# pH_mini_v30.net
KiCad netlist of a schematic drawn in EAGLE
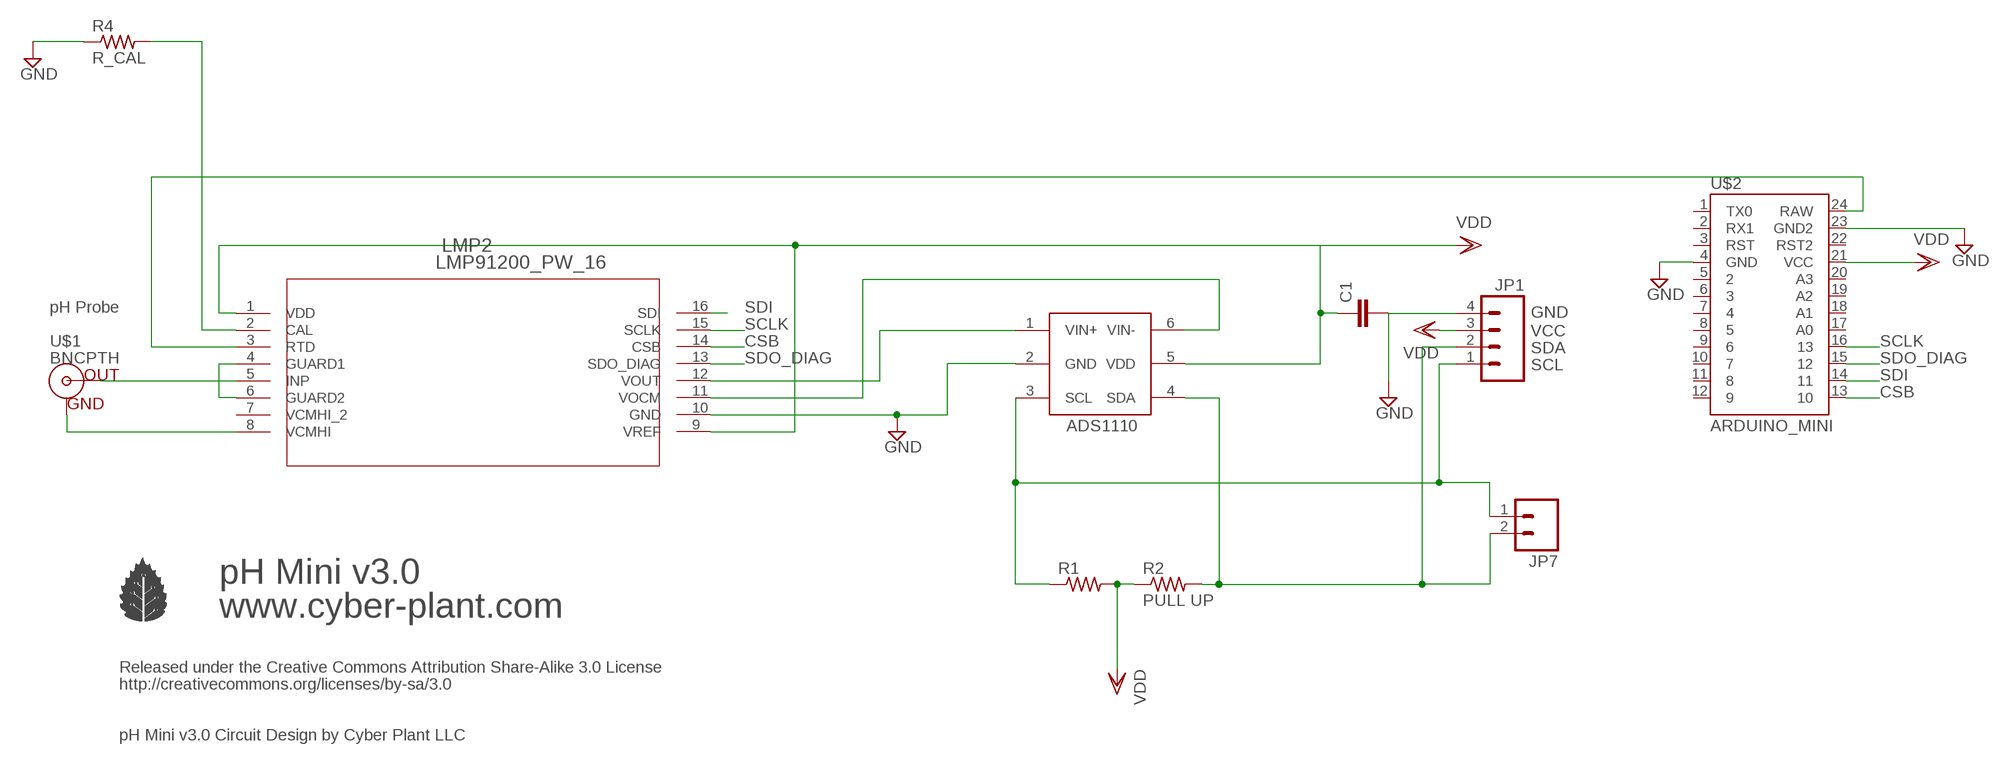
[diagram p0: schematic, sheet 1]

(export (version "E")
  (design (tool "Eeschema 10.0.6"))
  (components
    (comp (ref "C1")
      (value "CAP1206")
      (footprint "eagle-import:1206")
      (libsource (lib "eagle-import") (part "CAP1206"))
    )
    (comp (ref "IC1")
      (value "ADS1110")
      (footprint "eagle-import:SOT-23-6")
      (libsource (lib "eagle-import") (part "ADS1110"))
    )
    (comp (ref "JP1")
      (value "M04PTH")
      (footprint "eagle-import:1X04")
      (libsource (lib "eagle-import") (part "M04PTH"))
    )
    (comp (ref "JP7")
      (value "M02PTH")
      (footprint "eagle-import:1X02")
      (libsource (lib "eagle-import") (part "M02PTH"))
    )
    (comp (ref "LMP2")
      (value "LMP91200_PW_16")
      (footprint "eagle-import:MTC16")
      (fields
        (field (name "MANUFACTURER") "Texas Instruments")
        (field (name "MANUFACTURER_PART_NUMBER") "lmp91200_pw_16")
      )
      (libsource (lib "eagle-import") (part "LMP91200_PW_16"))
    )
    (comp (ref "R1")
      (value "R-US_0207/10")
      (footprint "eagle-import:0207_10")
      (libsource (lib "eagle-import") (part "R-US_0207/10"))
    )
    (comp (ref "R2")
      (value "PULL UP")
      (footprint "eagle-import:0207_10")
      (libsource (lib "eagle-import") (part "R-US_0207/10"))
    )
    (comp (ref "R4")
      (value "R_CAL")
      (footprint "eagle-import:0207_10")
      (libsource (lib "eagle-import") (part "R-US_0207/10"))
    )
    (comp (ref "U$1")
      (value "BNCPTH")
      (footprint "eagle-import:BNC")
      (libsource (lib "eagle-import") (part "BNCPTH"))
    )
    (comp (ref "U$2")
      (value "ARDUINO_MINI")
      (footprint "eagle-import:ARDUINO_MINI")
      (libsource (lib "eagle-import") (part "ARDUINO_MINI"))
    )
  )
  (nets
    (net (code "1") (name "/CSB") (class "Default")
      (node (ref "LMP2") (pin "14") (pinfunction "CSB_14") (pintype "passive"))
      (node (ref "U$2") (pin "13") (pinfunction "10_13") (pintype "bidirectional"))
    )
    (net (code "2") (name "/SCLK") (class "Default")
      (node (ref "LMP2") (pin "15") (pinfunction "SCLK_15") (pintype "passive"))
      (node (ref "U$2") (pin "16") (pinfunction "13_16") (pintype "bidirectional"))
    )
    (net (code "3") (name "/SDI") (class "Default")
      (node (ref "LMP2") (pin "16") (pinfunction "SDI_16") (pintype "passive"))
      (node (ref "U$2") (pin "14") (pinfunction "11_14") (pintype "bidirectional"))
    )
    (net (code "4") (name "/SDO_DIAG") (class "Default")
      (node (ref "LMP2") (pin "13") (pinfunction "SDO_DIAG_13") (pintype "bidirectional"))
      (node (ref "U$2") (pin "15") (pinfunction "12_15") (pintype "bidirectional"))
    )
    (net (code "5") (name "GND") (class "Default")
      (node (ref "C1") (pin "2") (pinfunction "2_2") (pintype "passive"))
      (node (ref "IC1") (pin "2") (pinfunction "GND_2") (pintype "bidirectional"))
      (node (ref "JP1") (pin "4") (pinfunction "4_4") (pintype "passive"))
      (node (ref "LMP2") (pin "10") (pinfunction "GND_10") (pintype "power_in"))
      (node (ref "R4") (pin "1") (pinfunction "1_1") (pintype "passive"))
      (node (ref "U$2") (pin "23") (pinfunction "GND2_23") (pintype "bidirectional"))
      (node (ref "U$2") (pin "4") (pinfunction "GND_4") (pintype "bidirectional"))
    )
    (net (code "6") (name "Net-(IC1-SCL)") (class "Default")
      (node (ref "IC1") (pin "3") (pinfunction "SCL_3") (pintype "bidirectional"))
      (node (ref "JP1") (pin "1") (pinfunction "1_1") (pintype "passive"))
      (node (ref "JP7") (pin "1") (pinfunction "1_1") (pintype "passive"))
      (node (ref "R1") (pin "1") (pinfunction "1_1") (pintype "passive"))
    )
    (net (code "7") (name "Net-(IC1-SDA)") (class "Default")
      (node (ref "IC1") (pin "4") (pinfunction "SDA_4") (pintype "bidirectional"))
      (node (ref "JP1") (pin "2") (pinfunction "2_2") (pintype "passive"))
      (node (ref "JP7") (pin "2") (pinfunction "2_2") (pintype "passive"))
      (node (ref "R2") (pin "2") (pinfunction "2_2") (pintype "passive"))
    )
    (net (code "8") (name "Net-(IC1-VIN+)") (class "Default")
      (node (ref "IC1") (pin "1") (pinfunction "VIN+_1") (pintype "bidirectional"))
      (node (ref "LMP2") (pin "12") (pinfunction "VOUT_12") (pintype "output"))
    )
    (net (code "9") (name "Net-(IC1-VIN-)") (class "Default")
      (node (ref "IC1") (pin "6") (pinfunction "VIN-_6") (pintype "bidirectional"))
      (node (ref "LMP2") (pin "11") (pinfunction "VOCM_11") (pintype "output"))
    )
    (net (code "10") (name "Net-(LMP2-CAL)") (class "Default")
      (node (ref "LMP2") (pin "2") (pinfunction "CAL_2") (pintype "passive"))
      (node (ref "R4") (pin "2") (pinfunction "2_2") (pintype "passive"))
    )
    (net (code "11") (name "Net-(LMP2-GUARD1)") (class "Default")
      (node (ref "LMP2") (pin "4") (pinfunction "GUARD1_4") (pintype "passive"))
      (node (ref "LMP2") (pin "6") (pinfunction "GUARD2_6") (pintype "passive"))
    )
    (net (code "12") (name "Net-(LMP2-INP)") (class "Default")
      (node (ref "LMP2") (pin "5") (pinfunction "INP_5") (pintype "input"))
      (node (ref "U$1") (pin "S") (pinfunction "OUT_S") (pintype "bidirectional"))
    )
    (net (code "13") (name "Net-(LMP2-RTD)") (class "Default")
      (node (ref "LMP2") (pin "3") (pinfunction "RTD_3") (pintype "bidirectional"))
      (node (ref "U$2") (pin "24") (pinfunction "RAW_24") (pintype "bidirectional"))
    )
    (net (code "14") (name "Net-(LMP2-VCMHI)") (class "Default")
      (node (ref "LMP2") (pin "8") (pinfunction "VCMHI_8") (pintype "output"))
      (node (ref "U$1") (pin "GND") (pinfunction "GND_GND") (pintype "bidirectional"))
    )
    (net (code "15") (name "VDD") (class "Default")
      (node (ref "C1") (pin "1") (pinfunction "1_1") (pintype "passive"))
      (node (ref "IC1") (pin "5") (pinfunction "VDD_5") (pintype "bidirectional"))
      (node (ref "JP1") (pin "3") (pinfunction "3_3") (pintype "passive"))
      (node (ref "LMP2") (pin "1") (pinfunction "VDD_1") (pintype "power_in"))
      (node (ref "LMP2") (pin "9") (pinfunction "VREF_9") (pintype "input"))
      (node (ref "R1") (pin "2") (pinfunction "2_2") (pintype "passive"))
      (node (ref "R2") (pin "1") (pinfunction "1_1") (pintype "passive"))
      (node (ref "U$2") (pin "21") (pinfunction "VCC_21") (pintype "bidirectional"))
    )
    (net (code "16") (name "unconnected-(LMP2-VCMHI_2-Pad7)") (class "Default")
      (node (ref "LMP2") (pin "7") (pinfunction "VCMHI_2_7") (pintype "output"))
    )
    (net (code "17") (name "unconnected-(U$2-2-Pad5)") (class "Default")
      (node (ref "U$2") (pin "5") (pinfunction "2_5") (pintype "bidirectional"))
    )
    (net (code "18") (name "unconnected-(U$2-3-Pad6)") (class "Default")
      (node (ref "U$2") (pin "6") (pinfunction "3_6") (pintype "bidirectional"))
    )
    (net (code "19") (name "unconnected-(U$2-4-Pad7)") (class "Default")
      (node (ref "U$2") (pin "7") (pinfunction "4_7") (pintype "bidirectional"))
    )
    (net (code "20") (name "unconnected-(U$2-5-Pad8)") (class "Default")
      (node (ref "U$2") (pin "8") (pinfunction "5_8") (pintype "bidirectional"))
    )
    (net (code "21") (name "unconnected-(U$2-6-Pad9)") (class "Default")
      (node (ref "U$2") (pin "9") (pinfunction "6_9") (pintype "bidirectional"))
    )
    (net (code "22") (name "unconnected-(U$2-7-Pad10)") (class "Default")
      (node (ref "U$2") (pin "10") (pinfunction "7_10") (pintype "bidirectional"))
    )
    (net (code "23") (name "unconnected-(U$2-8-Pad11)") (class "Default")
      (node (ref "U$2") (pin "11") (pinfunction "8_11") (pintype "bidirectional"))
    )
    (net (code "24") (name "unconnected-(U$2-9-Pad12)") (class "Default")
      (node (ref "U$2") (pin "12") (pinfunction "9_12") (pintype "bidirectional"))
    )
    (net (code "25") (name "unconnected-(U$2-A0-Pad17)") (class "Default")
      (node (ref "U$2") (pin "17") (pinfunction "A0_17") (pintype "bidirectional"))
    )
    (net (code "26") (name "unconnected-(U$2-A1-Pad18)") (class "Default")
      (node (ref "U$2") (pin "18") (pinfunction "A1_18") (pintype "bidirectional"))
    )
    (net (code "27") (name "unconnected-(U$2-A2-Pad19)") (class "Default")
      (node (ref "U$2") (pin "19") (pinfunction "A2_19") (pintype "bidirectional"))
    )
    (net (code "28") (name "unconnected-(U$2-A3-Pad20)") (class "Default")
      (node (ref "U$2") (pin "20") (pinfunction "A3_20") (pintype "bidirectional"))
    )
    (net (code "29") (name "unconnected-(U$2-RST-Pad3)") (class "Default")
      (node (ref "U$2") (pin "3") (pinfunction "RST_3") (pintype "bidirectional"))
    )
    (net (code "30") (name "unconnected-(U$2-RST2-Pad22)") (class "Default")
      (node (ref "U$2") (pin "22") (pinfunction "RST2_22") (pintype "bidirectional"))
    )
    (net (code "31") (name "unconnected-(U$2-RX1-Pad2)") (class "Default")
      (node (ref "U$2") (pin "2") (pinfunction "RX1_2") (pintype "bidirectional"))
    )
    (net (code "32") (name "unconnected-(U$2-TX0-Pad1)") (class "Default")
      (node (ref "U$2") (pin "1") (pinfunction "TX0_1") (pintype "bidirectional"))
    )
  )
)
